# EN_Probe_VR_Chain.net
KiCad netlist of a schematic drawn in Altium Designer
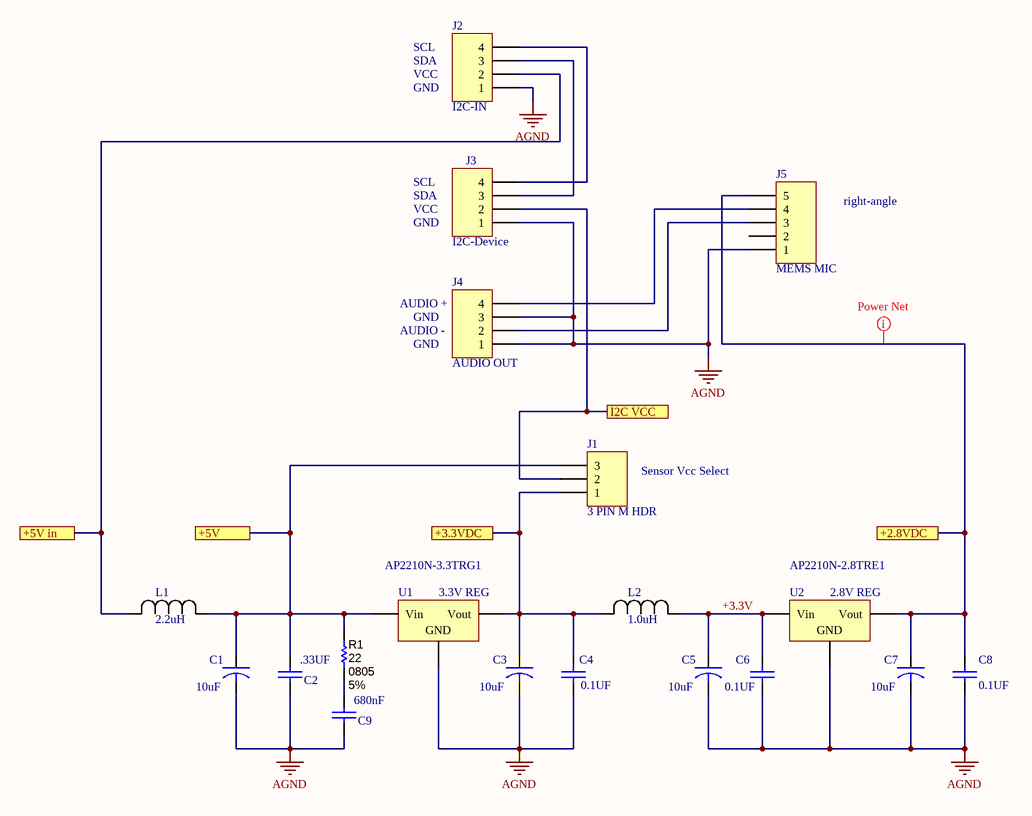
[diagram p0: EN_Probe_VR_Chain.SchDoc]

(export (version "E")
  (design (tool "Eeschema 10.0.6"))
  (components
    (comp (ref "C1")
      (value "10uF")
      (footprint "0805")
      (description "CAP CER 10UF 25V X5R 0805")
      (libsource (lib "*") (part "CAPACITOR"))
    )
    (comp (ref "C2")
      (value ".33UF")
      (footprint "0805")
      (description "CAP CER 0.33UF 25V X7R 0805")
      (libsource (lib "*") (part "CAP"))
    )
    (comp (ref "C3")
      (value "10uF")
      (footprint "0805")
      (description "CAP CER 10UF 25V X5R 0805")
      (libsource (lib "*") (part "CAPACITOR"))
    )
    (comp (ref "C4")
      (value "0.1UF")
      (footprint "0603")
      (description "CAP CER 0.1UF 50V X7R 0603")
      (libsource (lib "*") (part "CAP"))
    )
    (comp (ref "C5")
      (value "10uF")
      (footprint "0805")
      (description "CAP CER 10UF 25V X5R 0805")
      (libsource (lib "*") (part "CAPACITOR"))
    )
    (comp (ref "C6")
      (value "0.1UF")
      (footprint "0603")
      (description "CAP CER 0.1UF 50V X7R 0603")
      (libsource (lib "*") (part "CAP"))
    )
    (comp (ref "C7")
      (value "10uF")
      (footprint "0805")
      (description "CAP CER 10UF 25V X5R 0805")
      (libsource (lib "*") (part "CAPACITOR"))
    )
    (comp (ref "C8")
      (value "0.1UF")
      (footprint "0603")
      (description "CAP CER 0.1UF 50V X7R 0603")
      (libsource (lib "*") (part "CAP"))
    )
    (comp (ref "C9")
      (value "680nF")
      (footprint "0805")
      (description "CAP CER 0.33UF 25V X7R 0805")
      (libsource (lib "*") (part "CAP"))
    )
    (comp (ref "J1")
      (value "3 PIN M HDR")
      (footprint "HDR1X3")
      (description "3 Positions Header, Unshrouded, Breakaway Connector 0.100\" (2.54mm) Through Hole Gold")
      (fields (field (name "MANUFACTURER") "Harwin Inc."))
      (libsource (lib "altium") (part "CONN1X3"))
    )
    (comp (ref "J2")
      (value "I2C-IN")
      (footprint "HDRA1X4 2MM")
      (description "CONN HEADER VERT 4POS .100 TIN")
      (fields
        (field (name "MANUFACTURER") "TE Connectivity AMP Connectors")
        (field (name "PUBLISHER") "Altium Limited")
      )
      (libsource (lib "Miscellaneous Connectors") (part "Header 4"))
    )
    (comp (ref "J3")
      (value "I2C-Device")
      (footprint "HDRA1X4 2MM")
      (description "CONN HEADER VERT 4POS .100 TIN")
      (fields
        (field (name "MANUFACTURER") "TE Connectivity AMP Connectors")
        (field (name "PUBLISHER") "Altium Limited")
      )
      (libsource (lib "Miscellaneous Connectors") (part "Header 4"))
    )
    (comp (ref "J4")
      (value "AUDIO OUT")
      (footprint "HDRA1X4 2MM")
      (description "CONN HEADER VERT 4POS .100 TIN")
      (fields
        (field (name "MANUFACTURER") "TE Connectivity AMP Connectors")
        (field (name "PUBLISHER") "Altium Limited")
      )
      (libsource (lib "Miscellaneous Connectors") (part "Header 4"))
    )
    (comp (ref "J5")
      (value "MEMS MIC")
      (footprint "HDR1X5")
      (description "CONN HEADER VERT 5POS 2.54MM")
      (fields (field (name "MANUFACTURER") "Harwin Inc."))
      (libsource (lib "altium") (part "CONN1X5"))
    )
    (comp (ref "L1")
      (value "2.2uH")
      (footprint "1206")
      (description "FERRITE BEAD 160 OHM 1206 1LN")
      (fields
        (field (name "MANUFACTURER_PART_NUMBER") "HI1206T161R-10")
        (field (name "COPYRIGHT") "Copyright (C) 2018 Accelerated Designs. All rights reserved")
      )
      (libsource (lib "2020-08-13_00-23-02") (part "HI1206T161R-10"))
    )
    (comp (ref "L2")
      (value "1.0uH")
      (footprint "1206")
      (description "FERRITE BEAD 160 OHM 1206 1LN")
      (fields
        (field (name "MANUFACTURER_PART_NUMBER") "HI1206T161R-10")
        (field (name "COPYRIGHT") "Copyright (C) 2018 Accelerated Designs. All rights reserved")
      )
      (libsource (lib "2020-08-13_00-23-02") (part "HI1206T161R-10"))
    )
    (comp (ref "R1")
      (value "CRCW080522R0JNEA")
      (footprint "0805")
      (description "RES, 22, 5%, 0.125 W, 0805")
      (fields
        (field (name "MANUFACTURER") "Vishay-Dale")
        (field (name "VALUEDISPLAYED") "22")
        (field (name "PACKAGEREFERENCE") "0805")
        (field (name "VALUE1") "5%")
        (field (name "PUBLISHER") "Texas Instruments")
      )
      (libsource (lib "SugarCube SCADng_R3.1 40") (part "CRCW080522R0JNEA"))
    )
    (comp (ref "U1")
      (value "3.3V REG")
      (footprint "SOT23-3")
      (description "IC REG LINEAR 2.8V 300MA SOT23-3")
      (fields (field (name "PUBLISHER") "Altium Limited"))
      (libsource (lib "EN_Probe_VR") (part "Volt Reg"))
    )
    (comp (ref "U2")
      (value "2.8V REG")
      (footprint "SOT23-3")
      (description "IC REG LINEAR 2.8V 300MA SOT23-3")
      (fields (field (name "PUBLISHER") "Altium Limited"))
      (libsource (lib "EN_Probe_VR") (part "Volt Reg"))
    )
  )
  (nets
    (net (code "1") (name "/+2.8VDC") (class "Default")
      (node (ref "C7") (pin "1") (pinfunction "1_1") (pintype "passive"))
      (node (ref "C8") (pin "2") (pintype "passive"))
      (node (ref "J5") (pin "5") (pinfunction "5_5") (pintype "passive"))
      (node (ref "U2") (pin "2") (pinfunction "Vout_2") (pintype "passive"))
    )
    (net (code "2") (name "/+3.3V") (class "Default")
      (node (ref "C5") (pin "1") (pinfunction "1_1") (pintype "passive"))
      (node (ref "C6") (pin "2") (pintype "passive"))
      (node (ref "L2") (pin "1") (pinfunction "1_1") (pintype "passive"))
      (node (ref "U2") (pin "3") (pinfunction "Vin_3") (pintype "passive"))
    )
    (net (code "3") (name "/+3.3VDC") (class "Default")
      (node (ref "C3") (pin "1") (pinfunction "1_1") (pintype "passive"))
      (node (ref "C4") (pin "1") (pintype "passive"))
      (node (ref "J1") (pin "1") (pinfunction "1_1") (pintype "passive"))
      (node (ref "L2") (pin "2") (pinfunction "2_2") (pintype "passive"))
      (node (ref "U1") (pin "2") (pinfunction "Vout_2") (pintype "passive"))
    )
    (net (code "4") (name "/+5V") (class "Default")
      (node (ref "C1") (pin "1") (pinfunction "1_1") (pintype "passive"))
      (node (ref "C2") (pin "2") (pintype "passive"))
      (node (ref "J1") (pin "3") (pinfunction "3_3") (pintype "passive"))
      (node (ref "L1") (pin "1") (pinfunction "1_1") (pintype "passive"))
      (node (ref "R1") (pin "2") (pinfunction "2_2") (pintype "passive"))
      (node (ref "U1") (pin "3") (pinfunction "Vin_3") (pintype "passive"))
    )
    (net (code "5") (name "/+5V in") (class "Default")
      (node (ref "J2") (pin "2") (pinfunction "2_2") (pintype "passive"))
      (node (ref "L1") (pin "2") (pinfunction "2_2") (pintype "passive"))
    )
    (net (code "6") (name "/I2C VCC") (class "Default")
      (node (ref "J1") (pin "2") (pinfunction "2_2") (pintype "passive"))
      (node (ref "J3") (pin "2") (pinfunction "2_2") (pintype "passive"))
    )
    (net (code "7") (name "AGND") (class "Default")
      (node (ref "C1") (pin "2") (pinfunction "2_2") (pintype "passive"))
      (node (ref "C2") (pin "1") (pintype "passive"))
      (node (ref "C3") (pin "2") (pinfunction "2_2") (pintype "passive"))
      (node (ref "C4") (pin "2") (pintype "passive"))
      (node (ref "C5") (pin "2") (pinfunction "2_2") (pintype "passive"))
      (node (ref "C6") (pin "1") (pintype "passive"))
      (node (ref "C7") (pin "2") (pinfunction "2_2") (pintype "passive"))
      (node (ref "C8") (pin "1") (pintype "passive"))
      (node (ref "C9") (pin "1") (pintype "passive"))
      (node (ref "J2") (pin "1") (pinfunction "1_1") (pintype "passive"))
      (node (ref "J3") (pin "1") (pinfunction "1_1") (pintype "passive"))
      (node (ref "J4") (pin "1") (pinfunction "1_1") (pintype "passive"))
      (node (ref "J4") (pin "3") (pinfunction "3_3") (pintype "passive"))
      (node (ref "J5") (pin "1") (pinfunction "1_1") (pintype "passive"))
      (node (ref "U1") (pin "1") (pinfunction "GND_1") (pintype "passive"))
      (node (ref "U2") (pin "1") (pinfunction "GND_1") (pintype "passive"))
    )
    (net (code "8") (name "Net-(C9-Pad2)") (class "Default")
      (node (ref "C9") (pin "2") (pintype "passive"))
      (node (ref "R1") (pin "1") (pinfunction "1_1") (pintype "passive"))
    )
    (net (code "9") (name "Net-(J2-Pad3)") (class "Default")
      (node (ref "J2") (pin "3") (pinfunction "3_3") (pintype "passive"))
      (node (ref "J3") (pin "3") (pinfunction "3_3") (pintype "passive"))
    )
    (net (code "10") (name "Net-(J2-Pad4)") (class "Default")
      (node (ref "J2") (pin "4") (pinfunction "4_4") (pintype "passive"))
      (node (ref "J3") (pin "4") (pinfunction "4_4") (pintype "passive"))
    )
    (net (code "11") (name "Net-(J4-Pad2)") (class "Default")
      (node (ref "J4") (pin "2") (pinfunction "2_2") (pintype "passive"))
      (node (ref "J5") (pin "3") (pinfunction "3_3") (pintype "passive"))
    )
    (net (code "12") (name "Net-(J4-Pad4)") (class "Default")
      (node (ref "J4") (pin "4") (pinfunction "4_4") (pintype "passive"))
      (node (ref "J5") (pin "4") (pinfunction "4_4") (pintype "passive"))
    )
    (net (code "13") (name "unconnected-(J5-Pad2)") (class "Default")
      (node (ref "J5") (pin "2") (pinfunction "2_2") (pintype "passive"))
    )
  )
)
